# Rectifier_different_voltages.net
KiCad netlist of a schematic drawn in EAGLE
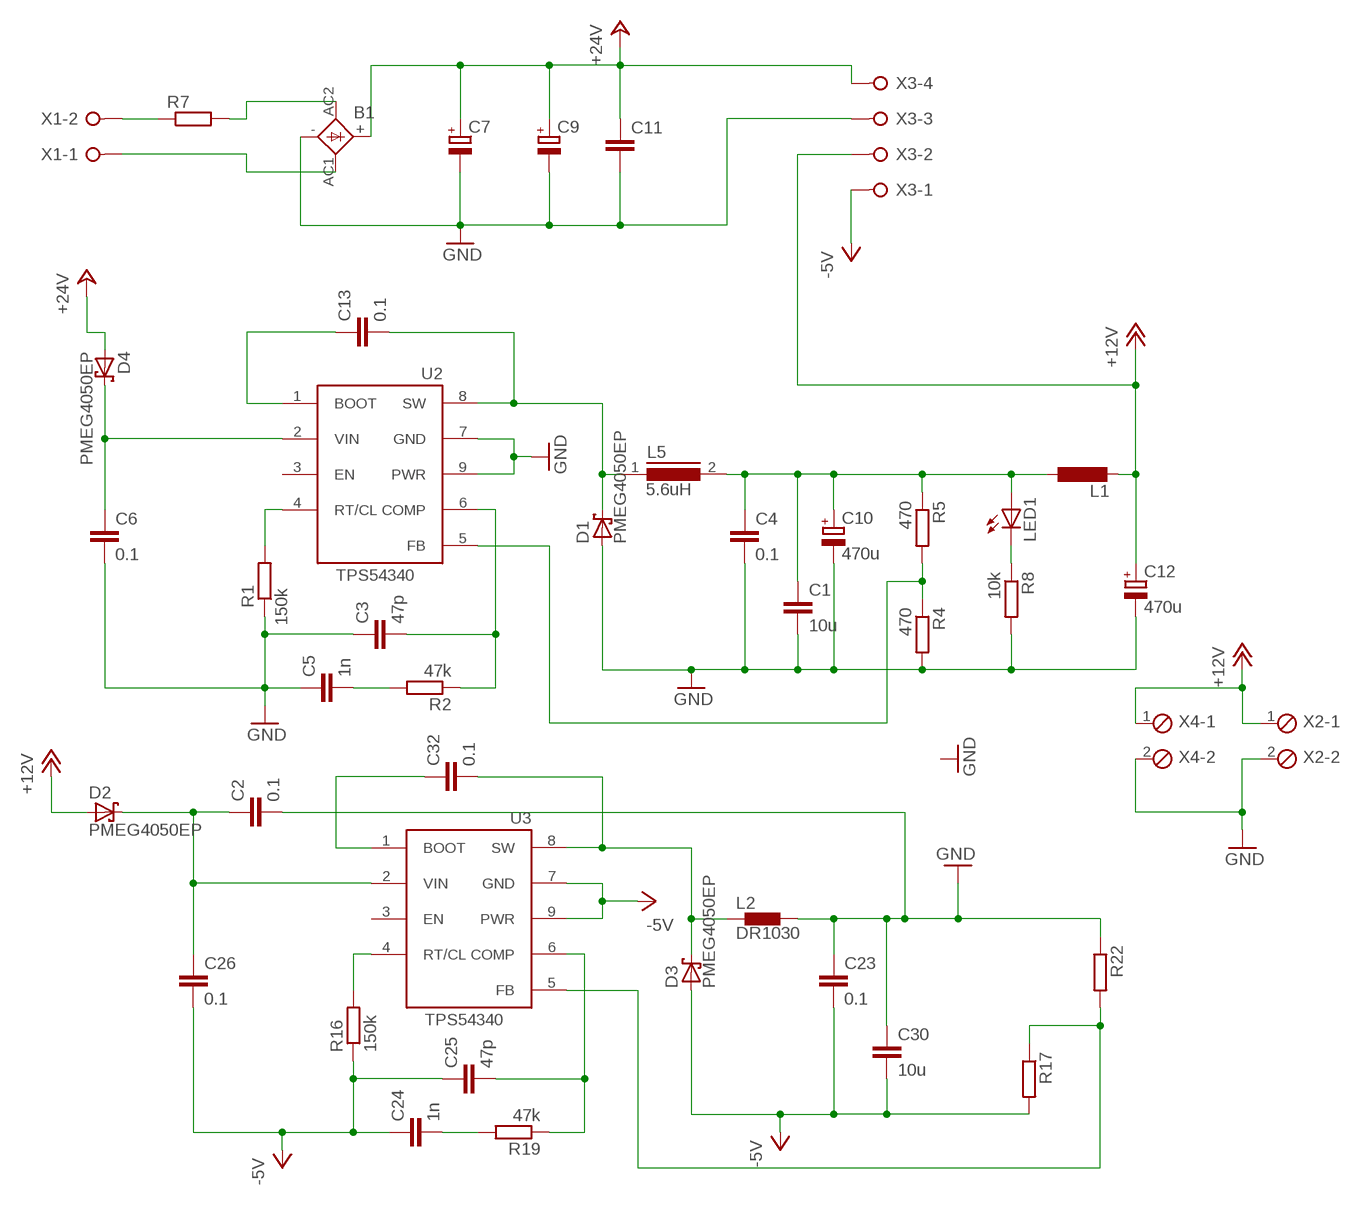
[diagram p0: schematic, sheet 1]

(export (version "E")
  (design (tool "Eeschema 10.0.6"))
  (components
    (comp (ref "B1")
      (value "KBL")
      (footprint "eagle-import:KBL")
      (libsource (lib "eagle-import") (part "KBL"))
    )
    (comp (ref "C1")
      (value "10u")
      (footprint "eagle-import:C1206")
      (libsource (lib "eagle-import") (part "C-EUC1206"))
    )
    (comp (ref "C2")
      (value "0.1")
      (footprint "eagle-import:C1210")
      (libsource (lib "eagle-import") (part "rcl_334_C-EUC1210"))
    )
    (comp (ref "C3")
      (value "47p")
      (footprint "eagle-import:C0603K")
      (libsource (lib "eagle-import") (part "rcl_334_C-EUC0603K"))
    )
    (comp (ref "C4")
      (value "0.1")
      (footprint "eagle-import:C1206")
      (libsource (lib "eagle-import") (part "C-EUC1206"))
    )
    (comp (ref "C5")
      (value "1n")
      (footprint "eagle-import:C0603K")
      (libsource (lib "eagle-import") (part "rcl_334_C-EUC0603K"))
    )
    (comp (ref "C6")
      (value "0.1")
      (footprint "eagle-import:C1206")
      (libsource (lib "eagle-import") (part "C-EUC1206"))
    )
    (comp (ref "C7")
      (value "CPOL-EUE7.5-18")
      (footprint "eagle-import:E7,5-18")
      (libsource (lib "eagle-import") (part "CPOL-EUE7.5-18"))
    )
    (comp (ref "C9")
      (value "CPOL-EUE7.5-18")
      (footprint "eagle-import:E7,5-18")
      (libsource (lib "eagle-import") (part "CPOL-EUE7.5-18"))
    )
    (comp (ref "C10")
      (value "470u")
      (footprint "eagle-import:E5-10,5")
      (libsource (lib "eagle-import") (part "CPOL-EUE5-10.5"))
    )
    (comp (ref "C11")
      (value "C-EUC1206")
      (footprint "eagle-import:C1206")
      (libsource (lib "eagle-import") (part "rcl_334_C-EUC1206"))
    )
    (comp (ref "C12")
      (value "470u")
      (footprint "eagle-import:E5-10,5")
      (libsource (lib "eagle-import") (part "CPOL-EUE5-10.5"))
    )
    (comp (ref "C13")
      (value "0.1")
      (footprint "eagle-import:C102-043X133")
      (libsource (lib "eagle-import") (part "rcl_334_C-EU102-043X133"))
    )
    (comp (ref "C23")
      (value "0.1")
      (footprint "eagle-import:C1206")
      (libsource (lib "eagle-import") (part "C-EUC1206"))
    )
    (comp (ref "C24")
      (value "1n")
      (footprint "eagle-import:C0603K")
      (libsource (lib "eagle-import") (part "rcl_334_C-EUC0603K"))
    )
    (comp (ref "C25")
      (value "47p")
      (footprint "eagle-import:C0603K")
      (libsource (lib "eagle-import") (part "rcl_334_C-EUC0603K"))
    )
    (comp (ref "C26")
      (value "0.1")
      (footprint "eagle-import:C1210")
      (libsource (lib "eagle-import") (part "rcl_334_C-EUC1210"))
    )
    (comp (ref "C30")
      (value "10u")
      (footprint "eagle-import:C1206")
      (libsource (lib "eagle-import") (part "C-EUC1206"))
    )
    (comp (ref "C32")
      (value "0.1")
      (footprint "eagle-import:C075-032X103")
      (libsource (lib "eagle-import") (part "rcl_334_C-EU075-032X103"))
    )
    (comp (ref "D1")
      (value "PMEG4050EP")
      (footprint "eagle-import:SOD128")
      (libsource (lib "eagle-import") (part "PMEG4050EP"))
    )
    (comp (ref "D2")
      (value "PMEG4050EP")
      (footprint "eagle-import:SOD128")
      (libsource (lib "eagle-import") (part "PMEG4050EP"))
    )
    (comp (ref "D3")
      (value "PMEG4050EP")
      (footprint "eagle-import:SOD128")
      (libsource (lib "eagle-import") (part "PMEG4050EP"))
    )
    (comp (ref "D4")
      (value "PMEG4050EP")
      (footprint "eagle-import:SOD128")
      (libsource (lib "eagle-import") (part "PMEG4050EP"))
    )
    (comp (ref "L1")
      (value "L-EU0207/5V")
      (footprint "eagle-import:0207_5V")
      (libsource (lib "eagle-import") (part "L-EU0207/5V"))
    )
    (comp (ref "L2")
      (value "DR1030")
      (footprint "eagle-import:DR1030")
      (libsource (lib "eagle-import") (part "DR1030"))
    )
    (comp (ref "L5")
      (value "5.6uH")
      (footprint "eagle-import:DR125")
      (libsource (lib "eagle-import") (part "DR125"))
    )
    (comp (ref "LED1")
      (value "LEDB152")
      (footprint "eagle-import:Q62902-B152")
      (libsource (lib "eagle-import") (part "LEDB152"))
    )
    (comp (ref "R1")
      (value "150k")
      (footprint "eagle-import:R1206")
      (libsource (lib "eagle-import") (part "R-EU_R1206"))
    )
    (comp (ref "R2")
      (value "47k")
      (footprint "eagle-import:R0603")
      (libsource (lib "eagle-import") (part "rcl_334_R-EU_R0603"))
    )
    (comp (ref "R4")
      (value "470")
      (footprint "eagle-import:R1206")
      (libsource (lib "eagle-import") (part "R-EU_R1206"))
    )
    (comp (ref "R5")
      (value "470")
      (footprint "eagle-import:R1206")
      (libsource (lib "eagle-import") (part "R-EU_R1206"))
    )
    (comp (ref "R7")
      (value "R-EU_0207/10")
      (footprint "eagle-import:0207_10")
      (libsource (lib "eagle-import") (part "rcl_334_R-EU_0207/10"))
    )
    (comp (ref "R8")
      (value "10k")
      (footprint "eagle-import:R0603")
      (libsource (lib "eagle-import") (part "rcl_334_R-EU_R0603"))
    )
    (comp (ref "R16")
      (value "150k")
      (footprint "eagle-import:R1206")
      (libsource (lib "eagle-import") (part "R-EU_R1206"))
    )
    (comp (ref "R17")
      (value "R-EU_R1206")
      (footprint "eagle-import:R1206")
      (libsource (lib "eagle-import") (part "R-EU_R1206"))
    )
    (comp (ref "R19")
      (value "47k")
      (footprint "eagle-import:R0603")
      (libsource (lib "eagle-import") (part "rcl_334_R-EU_R0603"))
    )
    (comp (ref "R22")
      (value "R-EU_R1206")
      (footprint "eagle-import:R1206")
      (libsource (lib "eagle-import") (part "R-EU_R1206"))
    )
    (comp (ref "U2")
      (value "TPS54340")
      (footprint "eagle-import:HSOP")
      (libsource (lib "eagle-import") (part "TPS54340SO8"))
    )
    (comp (ref "U3")
      (value "TPS54340SO8")
      (footprint "eagle-import:HSOP")
      (libsource (lib "eagle-import") (part "TPS54340SO8"))
    )
    (comp (ref "X1")
      (value "W237-02P")
      (footprint "eagle-import:W237-132")
      (libsource (lib "eagle-import") (part "W237-02P"))
    )
    (comp (ref "X2")
      (value "MPT2")
      (footprint "eagle-import:2POL254")
      (libsource (lib "eagle-import") (part "MPT2"))
    )
    (comp (ref "X3")
      (value "W237-04P")
      (footprint "eagle-import:W237-4P")
      (libsource (lib "eagle-import") (part "W237-04P"))
    )
    (comp (ref "X4")
      (value "MPT2")
      (footprint "eagle-import:2POL254")
      (libsource (lib "eagle-import") (part "MPT2"))
    )
  )
  (nets
    (net (code "1") (name "+12V") (class "Default")
      (node (ref "C12") (pin "+") (pinfunction "+_+") (pintype "passive"))
      (node (ref "D2") (pin "2") (pinfunction "A_2") (pintype "passive"))
      (node (ref "L1") (pin "2") (pinfunction "2_2") (pintype "passive"))
      (node (ref "X2") (pin "1") (pinfunction "1_1") (pintype "passive"))
      (node (ref "X3") (pin "2") (pinfunction "KL_2") (pintype "passive"))
      (node (ref "X4") (pin "1") (pinfunction "1_1") (pintype "passive"))
    )
    (net (code "2") (name "+24V") (class "Default")
      (node (ref "B1") (pin "+") (pinfunction "+_+") (pintype "passive"))
      (node (ref "C11") (pin "1") (pinfunction "1_1") (pintype "passive"))
      (node (ref "C7") (pin "+") (pinfunction "+_+") (pintype "passive"))
      (node (ref "C9") (pin "+") (pinfunction "+_+") (pintype "passive"))
      (node (ref "D4") (pin "2") (pinfunction "A_2") (pintype "passive"))
      (node (ref "X3") (pin "4") (pinfunction "KL_4") (pintype "passive"))
    )
    (net (code "3") (name "-5V") (class "Default")
      (node (ref "C23") (pin "2") (pinfunction "2_2") (pintype "passive"))
      (node (ref "C24") (pin "1") (pinfunction "1_1") (pintype "passive"))
      (node (ref "C25") (pin "1") (pinfunction "1_1") (pintype "passive"))
      (node (ref "C26") (pin "2") (pinfunction "2_2") (pintype "passive"))
      (node (ref "C30") (pin "2") (pinfunction "2_2") (pintype "passive"))
      (node (ref "D3") (pin "2") (pinfunction "A_2") (pintype "passive"))
      (node (ref "R16") (pin "1") (pinfunction "1_1") (pintype "passive"))
      (node (ref "R17") (pin "2") (pinfunction "2_2") (pintype "passive"))
      (node (ref "U3") (pin "7") (pinfunction "GND_7") (pintype "power_in"))
      (node (ref "U3") (pin "9") (pinfunction "PWR_9") (pintype "power_in"))
      (node (ref "X3") (pin "1") (pinfunction "KL_1") (pintype "passive"))
    )
    (net (code "4") (name "GND") (class "Default")
      (node (ref "B1") (pin "-") (pinfunction "-_-") (pintype "passive"))
      (node (ref "C1") (pin "2") (pinfunction "2_2") (pintype "passive"))
      (node (ref "C10") (pin "-") (pinfunction "-_-") (pintype "passive"))
      (node (ref "C11") (pin "2") (pinfunction "2_2") (pintype "passive"))
      (node (ref "C12") (pin "-") (pinfunction "-_-") (pintype "passive"))
      (node (ref "C2") (pin "2") (pinfunction "2_2") (pintype "passive"))
      (node (ref "C23") (pin "1") (pinfunction "1_1") (pintype "passive"))
      (node (ref "C3") (pin "1") (pinfunction "1_1") (pintype "passive"))
      (node (ref "C30") (pin "1") (pinfunction "1_1") (pintype "passive"))
      (node (ref "C4") (pin "2") (pinfunction "2_2") (pintype "passive"))
      (node (ref "C5") (pin "1") (pinfunction "1_1") (pintype "passive"))
      (node (ref "C6") (pin "2") (pinfunction "2_2") (pintype "passive"))
      (node (ref "C7") (pin "-") (pinfunction "-_-") (pintype "passive"))
      (node (ref "C9") (pin "-") (pinfunction "-_-") (pintype "passive"))
      (node (ref "D1") (pin "2") (pinfunction "A_2") (pintype "passive"))
      (node (ref "L2") (pin "2") (pinfunction "2_2") (pintype "passive"))
      (node (ref "R1") (pin "1") (pinfunction "1_1") (pintype "passive"))
      (node (ref "R22") (pin "1") (pinfunction "1_1") (pintype "passive"))
      (node (ref "R4") (pin "2") (pinfunction "2_2") (pintype "passive"))
      (node (ref "R8") (pin "2") (pinfunction "2_2") (pintype "passive"))
      (node (ref "U2") (pin "7") (pinfunction "GND_7") (pintype "power_in"))
      (node (ref "U2") (pin "9") (pinfunction "PWR_9") (pintype "power_in"))
      (node (ref "X2") (pin "2") (pinfunction "1_2") (pintype "passive"))
      (node (ref "X3") (pin "3") (pinfunction "KL_3") (pintype "passive"))
      (node (ref "X4") (pin "2") (pinfunction "1_2") (pintype "passive"))
    )
    (net (code "5") (name "Net-(B1-AC1)") (class "Default")
      (node (ref "B1") (pin "AC2") (pinfunction "AC1_AC2") (pintype "passive"))
      (node (ref "R7") (pin "2") (pinfunction "2_2") (pintype "passive"))
    )
    (net (code "6") (name "Net-(B1-AC2)") (class "Default")
      (node (ref "B1") (pin "AC1") (pinfunction "AC2_AC1") (pintype "passive"))
      (node (ref "X1") (pin "1") (pinfunction "KL_1") (pintype "passive"))
    )
    (net (code "7") (name "Net-(C1-Pad1)") (class "Default")
      (node (ref "C1") (pin "1") (pinfunction "1_1") (pintype "passive"))
      (node (ref "C10") (pin "+") (pinfunction "+_+") (pintype "passive"))
      (node (ref "C4") (pin "1") (pinfunction "1_1") (pintype "passive"))
      (node (ref "L1") (pin "1") (pinfunction "1_1") (pintype "passive"))
      (node (ref "L5") (pin "2") (pinfunction "2_2") (pintype "passive"))
      (node (ref "LED1") (pin "A") (pinfunction "A_A") (pintype "passive"))
      (node (ref "R5") (pin "1") (pinfunction "1_1") (pintype "passive"))
    )
    (net (code "8") (name "Net-(C5-Pad2)") (class "Default")
      (node (ref "C5") (pin "2") (pinfunction "2_2") (pintype "passive"))
      (node (ref "R2") (pin "2") (pinfunction "2_2") (pintype "passive"))
    )
    (net (code "9") (name "Net-(C24-Pad2)") (class "Default")
      (node (ref "C24") (pin "2") (pinfunction "2_2") (pintype "passive"))
      (node (ref "R19") (pin "2") (pinfunction "2_2") (pintype "passive"))
    )
    (net (code "10") (name "Net-(D1-K)") (class "Default")
      (node (ref "C13") (pin "2") (pinfunction "2_2") (pintype "passive"))
      (node (ref "D1") (pin "1") (pinfunction "K_1") (pintype "passive"))
      (node (ref "L5") (pin "1") (pinfunction "1_1") (pintype "passive"))
      (node (ref "U2") (pin "8") (pinfunction "SW_8") (pintype "power_in"))
    )
    (net (code "11") (name "Net-(D2-K)") (class "Default")
      (node (ref "C2") (pin "1") (pinfunction "1_1") (pintype "passive"))
      (node (ref "C26") (pin "1") (pinfunction "1_1") (pintype "passive"))
      (node (ref "D2") (pin "1") (pinfunction "K_1") (pintype "passive"))
      (node (ref "U3") (pin "2") (pinfunction "VIN_2") (pintype "power_in"))
    )
    (net (code "12") (name "Net-(D3-K)") (class "Default")
      (node (ref "C32") (pin "2") (pinfunction "2_2") (pintype "passive"))
      (node (ref "D3") (pin "1") (pinfunction "K_1") (pintype "passive"))
      (node (ref "L2") (pin "1") (pinfunction "1_1") (pintype "passive"))
      (node (ref "U3") (pin "8") (pinfunction "SW_8") (pintype "power_in"))
    )
    (net (code "13") (name "Net-(D4-K)") (class "Default")
      (node (ref "C6") (pin "1") (pinfunction "1_1") (pintype "passive"))
      (node (ref "D4") (pin "1") (pinfunction "K_1") (pintype "passive"))
      (node (ref "U2") (pin "2") (pinfunction "VIN_2") (pintype "power_in"))
    )
    (net (code "14") (name "Net-(LED1-C)") (class "Default")
      (node (ref "LED1") (pin "K") (pinfunction "C_K") (pintype "passive"))
      (node (ref "R8") (pin "1") (pinfunction "1_1") (pintype "passive"))
    )
    (net (code "15") (name "Net-(U2-BOOT)") (class "Default")
      (node (ref "C13") (pin "1") (pinfunction "1_1") (pintype "passive"))
      (node (ref "U2") (pin "1") (pinfunction "BOOT_1") (pintype "input"))
    )
    (net (code "16") (name "Net-(U2-COMP)") (class "Default")
      (node (ref "C3") (pin "2") (pinfunction "2_2") (pintype "passive"))
      (node (ref "R2") (pin "1") (pinfunction "1_1") (pintype "passive"))
      (node (ref "U2") (pin "6") (pinfunction "COMP_6") (pintype "input"))
    )
    (net (code "17") (name "Net-(U2-FB)") (class "Default")
      (node (ref "R4") (pin "1") (pinfunction "1_1") (pintype "passive"))
      (node (ref "R5") (pin "2") (pinfunction "2_2") (pintype "passive"))
      (node (ref "U2") (pin "5") (pinfunction "FB_5") (pintype "input"))
    )
    (net (code "18") (name "Net-(U2-RT{slash}CL)") (class "Default")
      (node (ref "R1") (pin "2") (pinfunction "2_2") (pintype "passive"))
      (node (ref "U2") (pin "4") (pinfunction "RT/CL_4") (pintype "input"))
    )
    (net (code "19") (name "Net-(U3-BOOT)") (class "Default")
      (node (ref "C32") (pin "1") (pinfunction "1_1") (pintype "passive"))
      (node (ref "U3") (pin "1") (pinfunction "BOOT_1") (pintype "input"))
    )
    (net (code "20") (name "Net-(U3-COMP)") (class "Default")
      (node (ref "C25") (pin "2") (pinfunction "2_2") (pintype "passive"))
      (node (ref "R19") (pin "1") (pinfunction "1_1") (pintype "passive"))
      (node (ref "U3") (pin "6") (pinfunction "COMP_6") (pintype "input"))
    )
    (net (code "21") (name "Net-(U3-FB)") (class "Default")
      (node (ref "R17") (pin "1") (pinfunction "1_1") (pintype "passive"))
      (node (ref "R22") (pin "2") (pinfunction "2_2") (pintype "passive"))
      (node (ref "U3") (pin "5") (pinfunction "FB_5") (pintype "input"))
    )
    (net (code "22") (name "Net-(U3-RT{slash}CL)") (class "Default")
      (node (ref "R16") (pin "2") (pinfunction "2_2") (pintype "passive"))
      (node (ref "U3") (pin "4") (pinfunction "RT/CL_4") (pintype "input"))
    )
    (net (code "23") (name "Net-(X1B-KL)") (class "Default")
      (node (ref "R7") (pin "1") (pinfunction "1_1") (pintype "passive"))
      (node (ref "X1") (pin "2") (pinfunction "KL_2") (pintype "passive"))
    )
    (net (code "24") (name "unconnected-(U2-EN-Pad3)") (class "Default")
      (node (ref "U2") (pin "3") (pinfunction "EN_3") (pintype "input"))
    )
    (net (code "25") (name "unconnected-(U3-EN-Pad3)") (class "Default")
      (node (ref "U3") (pin "3") (pinfunction "EN_3") (pintype "input"))
    )
  )
)
